# Pg07__DDR3_Memory.net
KiCad netlist of a schematic drawn in Altium Designer
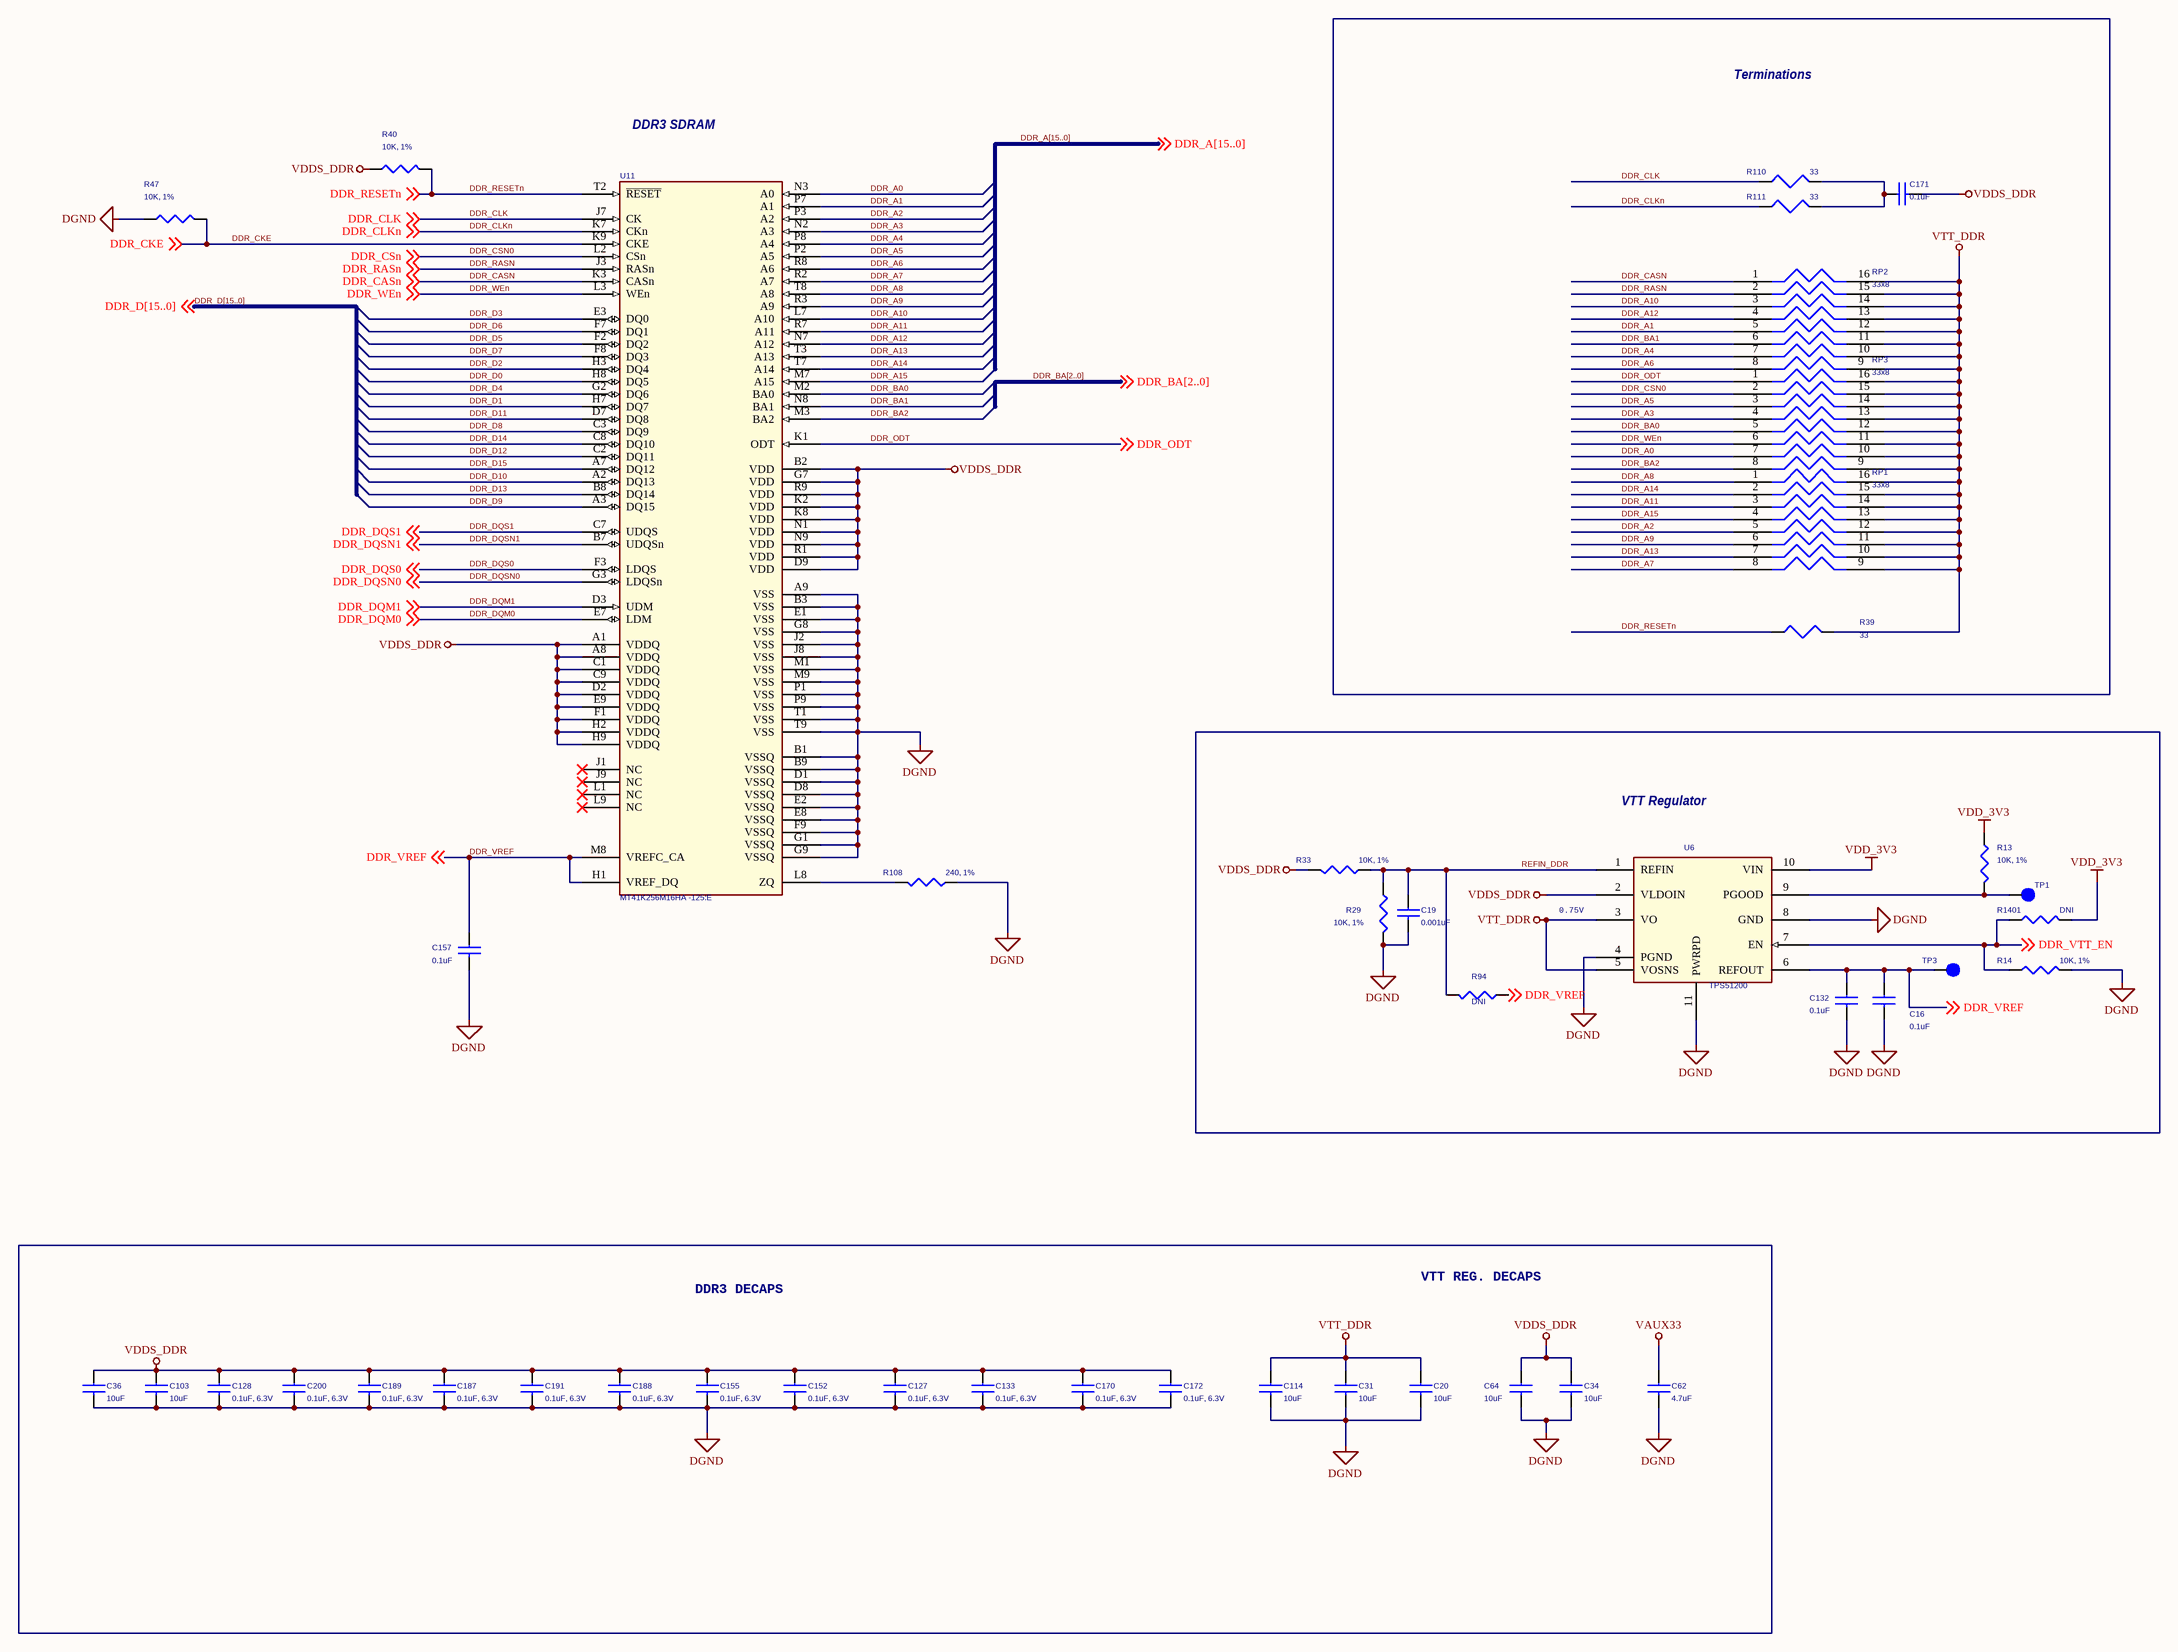
[diagram p0: Pg07_ DDR3_Memory.SchDoc]

(export (version "E")
  (design (tool "Eeschema 10.0.6"))
  (components
    (comp (ref "C16")
      (value "0.1uF")
      (footprint "SM-7351-CAP-0402")
      (fields (field (name "TIINTPARTNUMBER") "1C0089") (field (name "MFR") "Kemet"))
      (libsource (lib "*") (part "0.1uFCapacitor16V10%0402_Dup1"))
    )
    (comp (ref "C19")
      (value "0.001uF")
      (footprint "SM-7351-CAP-0402")
      (fields (field (name "MFR") "AVX") (field (name "TIINTPARTNUMBER") "1C0093"))
      (libsource (lib "*") (part "0.001uFCapacitor50V5%0402"))
    )
    (comp (ref "C20")
      (value "10uF")
      (footprint "SM-7351-CAP-0805")
      (description "Capacitor 10uF 16V 10% Ceramic 0805")
      (fields (field (name "MFR") "AVX") (field (name "TIINTPARTNUMBER") "1C0085"))
      (libsource (lib "*") (part "10uFCapacitor16V10%0805"))
    )
    (comp (ref "C31")
      (value "10uF")
      (footprint "SM-7351-CAP-0805")
      (description "Capacitor 10uF 16V 10% Ceramic 0805")
      (fields (field (name "MFR") "AVX") (field (name "TIINTPARTNUMBER") "1C0085"))
      (libsource (lib "*") (part "10uFCapacitor16V10%0805"))
    )
    (comp (ref "C34")
      (value "10uF")
      (footprint "SM-7351-CAP-0805")
      (description "Capacitor 10uF 16V 10% Ceramic 0805")
      (fields (field (name "MFR") "AVX") (field (name "TIINTPARTNUMBER") "1C0085"))
      (libsource (lib "*") (part "10uFCapacitor16V10%0805"))
    )
    (comp (ref "C36")
      (value "10uF")
      (footprint "SM-7351-CAP-0805")
      (description "Capacitor 10uF 16V 10% Ceramic 0805")
      (fields (field (name "MFR") "AVX") (field (name "TIINTPARTNUMBER") "1C0085"))
      (libsource (lib "*") (part "10uFCapacitor16V10%0805"))
    )
    (comp (ref "C62")
      (value "4.7uF")
      (footprint "SM-7351-CAP-0603")
      (fields (field (name "TIINTPARTNUMBER") "1C0103") (field (name "MFR") "Taiyo Yuden"))
      (libsource (lib "*") (part "4.7uFCapacitor16V10%0603"))
    )
    (comp (ref "C64")
      (value "10uF")
      (footprint "SM-7351-CAP-0805")
      (description "Capacitor 10uF 16V 10% Ceramic 0805")
      (fields (field (name "MFR") "AVX") (field (name "TIINTPARTNUMBER") "1C0085"))
      (libsource (lib "*") (part "10uFCapacitor16V10%0805"))
    )
    (comp (ref "C103")
      (value "10uF")
      (footprint "SM-7351-CAP-0805")
      (description "Capacitor 10uF 16V 10% Ceramic 0805")
      (fields (field (name "MFR") "AVX") (field (name "TIINTPARTNUMBER") "1C0085"))
      (libsource (lib "*") (part "10uFCapacitor16V10%0805"))
    )
    (comp (ref "C114")
      (value "10uF")
      (footprint "SM-7351-CAP-0805")
      (description "Capacitor 10uF 16V 10% Ceramic 0805")
      (fields (field (name "MFR") "AVX") (field (name "TIINTPARTNUMBER") "1C0085"))
      (libsource (lib "*") (part "10uFCapacitor16V10%0805"))
    )
    (comp (ref "C127")
      (value "0.1uF, 6.3V")
      (footprint "SM-7351-CAP-0402")
      (fields (field (name "MFR") "Murata") (field (name "TIINTPARTNUMBER") "1C0122"))
      (libsource (lib "*") (part "0.1uFCapacitor6.3V10%0201"))
    )
    (comp (ref "C128")
      (value "0.1uF, 6.3V")
      (footprint "SM-7351-CAP-0402")
      (fields (field (name "MFR") "Murata") (field (name "TIINTPARTNUMBER") "1C0122"))
      (libsource (lib "*") (part "0.1uFCapacitor6.3V10%0201"))
    )
    (comp (ref "C132")
      (value "0.1uF")
      (footprint "SM-7351-CAP-0402")
      (fields (field (name "TIINTPARTNUMBER") "1C0089") (field (name "MFR") "Kemet"))
      (libsource (lib "*") (part "0.1uFCapacitor16V10%0402_Dup1"))
    )
    (comp (ref "C133")
      (value "0.1uF, 6.3V")
      (footprint "SMD0201")
      (fields (field (name "MFR") "Murata") (field (name "TIINTPARTNUMBER") "1C0122"))
      (libsource (lib "*") (part "0.1uFCapacitor6.3V10%0201"))
    )
    (comp (ref "C152")
      (value "0.1uF, 6.3V")
      (footprint "SM-7351-CAP-0402")
      (fields (field (name "MFR") "Murata") (field (name "TIINTPARTNUMBER") "1C0122"))
      (libsource (lib "*") (part "0.1uFCapacitor6.3V10%0201"))
    )
    (comp (ref "C155")
      (value "0.1uF, 6.3V")
      (footprint "SMD0201")
      (fields (field (name "MFR") "Murata") (field (name "TIINTPARTNUMBER") "1C0122"))
      (libsource (lib "*") (part "0.1uFCapacitor6.3V10%0201"))
    )
    (comp (ref "C157")
      (value "0.1uF")
      (footprint "SM-7351-CAP-0402")
      (fields (field (name "TIINTPARTNUMBER") "1C0089") (field (name "MFR") "Kemet"))
      (libsource (lib "*") (part "0.1uFCapacitor16V10%0402_Dup1"))
    )
    (comp (ref "C170")
      (value "0.1uF, 6.3V")
      (footprint "SM-7351-CAP-0402")
      (fields (field (name "MFR") "Murata") (field (name "TIINTPARTNUMBER") "1C0122"))
      (libsource (lib "*") (part "0.1uFCapacitor6.3V10%0201"))
    )
    (comp (ref "C171")
      (value "0.1uF")
      (footprint "SM-7351-CAP-0402")
      (fields (field (name "TIINTPARTNUMBER") "1C0089") (field (name "MFR") "Kemet"))
      (libsource (lib "*") (part "0.1uFCapacitor16V10%0402_Dup1"))
    )
    (comp (ref "C172")
      (value "0.1uF, 6.3V")
      (footprint "SM-7351-CAP-0402")
      (fields (field (name "MFR") "Murata") (field (name "TIINTPARTNUMBER") "1C0122"))
      (libsource (lib "*") (part "0.1uFCapacitor6.3V10%0201"))
    )
    (comp (ref "C187")
      (value "0.1uF, 6.3V")
      (footprint "SM-7351-CAP-0402")
      (fields (field (name "MFR") "Murata") (field (name "TIINTPARTNUMBER") "1C0122"))
      (libsource (lib "*") (part "0.1uFCapacitor6.3V10%0201"))
    )
    (comp (ref "C188")
      (value "0.1uF, 6.3V")
      (footprint "SM-7351-CAP-0402")
      (fields (field (name "MFR") "Murata") (field (name "TIINTPARTNUMBER") "1C0122"))
      (libsource (lib "*") (part "0.1uFCapacitor6.3V10%0201"))
    )
    (comp (ref "C189")
      (value "0.1uF, 6.3V")
      (footprint "SM-7351-CAP-0402")
      (fields (field (name "MFR") "Murata") (field (name "TIINTPARTNUMBER") "1C0122"))
      (libsource (lib "*") (part "0.1uFCapacitor6.3V10%0201"))
    )
    (comp (ref "C191")
      (value "0.1uF, 6.3V")
      (footprint "SM-7351-CAP-0402")
      (fields (field (name "MFR") "Murata") (field (name "TIINTPARTNUMBER") "1C0122"))
      (libsource (lib "*") (part "0.1uFCapacitor6.3V10%0201"))
    )
    (comp (ref "C200")
      (value "0.1uF, 6.3V")
      (footprint "SMD0201")
      (fields (field (name "MFR") "Murata") (field (name "TIINTPARTNUMBER") "1C0122"))
      (libsource (lib "*") (part "0.1uFCapacitor6.3V10%0201"))
    )
    (comp (ref "R13")
      (value "10K, 1%")
      (footprint "SM-7351-RES-0402")
      (fields (field (name "TIINTPARTNUMBER") "1R0254") (field (name "MFR") "Panasonic-ECG"))
      (libsource (lib "*") (part "10KOhmResistor1/10W1%0402_Dup3"))
    )
    (comp (ref "R14")
      (value "10K, 1%")
      (footprint "SM-7351-RES-0402")
      (fields (field (name "TIINTPARTNUMBER") "1R0254") (field (name "MFR") "Panasonic-ECG"))
      (libsource (lib "*") (part "10KOhmResistor1/10W1%0402"))
    )
    (comp (ref "R29")
      (value "10K, 1%")
      (footprint "SM-7351-RES-0402")
      (fields (field (name "TIINTPARTNUMBER") "1R0254") (field (name "MFR") "Panasonic-ECG"))
      (libsource (lib "*") (part "10KOhmResistor1/10W1%0402_Dup3"))
    )
    (comp (ref "R33")
      (value "10K, 1%")
      (footprint "SM-7351-RES-0402")
      (fields (field (name "TIINTPARTNUMBER") "1R0254") (field (name "MFR") "Panasonic-ECG"))
      (libsource (lib "*") (part "10KOhmResistor1/10W1%0402_Dup3"))
    )
    (comp (ref "R39")
      (value "33")
      (footprint "SM-7351-RES-0402")
      (description "Resistor 33ohm 1/16W 5% 0402")
      (fields (field (name "MFR") "Panasonic") (field (name "TIINTPARTNUMBER") "1R0008"))
      (libsource (lib "*") (part "33ohmResistor1/16W5%0402"))
    )
    (comp (ref "R40")
      (value "10K, 1%")
      (footprint "SM-7351-RES-0402")
      (fields (field (name "TIINTPARTNUMBER") "1R0254") (field (name "MFR") "PANASONIC-ECG"))
      (libsource (lib "*") (part "10KOhmResistor1/10W1%0402_Dup1"))
    )
    (comp (ref "R47")
      (value "10K, 1%")
      (footprint "SM-7351-RES-0402")
      (fields (field (name "TIINTPARTNUMBER") "1R0254") (field (name "MFR") "PANASONIC-ECG"))
      (libsource (lib "*") (part "10KOhmResistor1/10W1%0402_Dup1"))
    )
    (comp (ref "R94")
      (value "DNI")
      (footprint "SM-7351-RES-0402")
      (fields (field (name "TIINTPARTNUMBER") "1R0254") (field (name "MFR") "Panasonic-ECG"))
      (libsource (lib "*") (part "10KOhmResistor1/10W1%0402_Dup3"))
    )
    (comp (ref "R108")
      (value "240, 1%")
      (footprint "SM-7351-RES-0402")
      (fields (field (name "MFR") "Panasonic-ECG") (field (name "TIINTPARTNUMBER") "1R0249"))
      (libsource (lib "*") (part "240OhmResistor1/10W1%0402"))
    )
    (comp (ref "R110")
      (value "33")
      (footprint "SM-7351-RES-0402")
      (description "Resistor 33ohm 1/16W 5% 0402")
      (fields (field (name "MFR") "Panasonic") (field (name "TIINTPARTNUMBER") "1R0008"))
      (libsource (lib "*") (part "33ohmResistor1/16W5%0402"))
    )
    (comp (ref "R111")
      (value "33")
      (footprint "SM-7351-RES-0402")
      (description "Resistor 33ohm 1/16W 5% 0402")
      (fields (field (name "MFR") "Panasonic") (field (name "TIINTPARTNUMBER") "1R0008"))
      (libsource (lib "*") (part "33ohmResistor1/16W5%0402"))
    )
    (comp (ref "R1401")
      (value "DNI")
      (footprint "SM-7351-RES-0402")
      (fields (field (name "TIINTPARTNUMBER") "1R0254") (field (name "MFR") "Panasonic-ECG"))
      (libsource (lib "*") (part "10KOhmResistor1/10W1%0402"))
    )
    (comp (ref "RP1")
      (value "33x8")
      (footprint "sm_rpak_exb-2hv")
      (description "Resistor 33ohmx8 1/16W 5% Array SMD")
      (fields (field (name "MFR") "Panasonic") (field (name "TIINTPARTNUMBER") "1R0196"))
      (libsource (lib "*") (part "33ohmx8_1/16W5%smd"))
    )
    (comp (ref "RP2")
      (value "33x8")
      (footprint "sm_rpak_exb-2hv")
      (description "Resistor 33ohmx8 1/16W 5% Array SMD")
      (fields (field (name "MFR") "Panasonic") (field (name "TIINTPARTNUMBER") "1R0196"))
      (libsource (lib "*") (part "33ohmx8_1/16W5%smd"))
    )
    (comp (ref "RP3")
      (value "33x8")
      (footprint "sm_rpak_exb-2hv")
      (description "Resistor 33ohmx8 1/16W 5% Array SMD")
      (fields (field (name "MFR") "Panasonic") (field (name "TIINTPARTNUMBER") "1R0196"))
      (libsource (lib "*") (part "33ohmx8_1/16W5%smd"))
    )
    (comp (ref "TP1")
      (value "TP1mm")
      (footprint "tp_smd1mmcircle")
      (description "Testpoint SMD 1mm circle pad")
      (fields (field (name "TIINTPARTNUMBER") "2H0046"))
      (libsource (lib "*") (part "Testpoint_SMD1mmCircle"))
    )
    (comp (ref "TP3")
      (value "TP1mm")
      (footprint "tp_smd1mmcircle")
      (description "Testpoint SMD 1mm circle pad")
      (fields (field (name "TIINTPARTNUMBER") "2H0046"))
      (libsource (lib "*") (part "Testpoint_SMD1mmCircle"))
    )
    (comp (ref "U6")
      (value "TPS51200")
      (footprint "SON10")
      (fields (field (name "TIINTPARTNUMBER") "1A0297") (field (name "MFR") "TI"))
      (libsource (lib "*") (part "TPS51200"))
    )
    (comp (ref "U11")
      (value "MT41K256M16HA -125:E")
      (footprint "BGA14X10-96")
      (description "DDR2 SDRAM 2Gb (256Mx8)")
      (fields
        (field (name "MANUFACTURER") "Micron Technology")
        (field (name "MANUFACTURER PART NUMBER") "MT41K256M16HA-125:E")
      )
      (libsource (lib "BEAGLEBONEBLACK_REV A5B") (part "MT41K256M16HA"))
    )
  )
  (nets
    (net (code "1") (name "/REFIN_DDR") (class "Default")
      (node (ref "C19") (pin "1") (pinfunction "1_1") (pintype "passive"))
      (node (ref "R29") (pin "1") (pinfunction "1_1") (pintype "passive"))
      (node (ref "R33") (pin "1") (pinfunction "1_1") (pintype "passive"))
      (node (ref "R94") (pin "2") (pinfunction "2_2") (pintype "passive"))
      (node (ref "U6") (pin "1") (pinfunction "REFIN_1") (pintype "passive"))
    )
    (net (code "2") (name "DDR_A0") (class "Default")
      (node (ref "RP3") (pin "7") (pinfunction "7_7") (pintype "passive"))
      (node (ref "U11") (pin "N3") (pinfunction "A0_N3") (pintype "input"))
    )
    (net (code "3") (name "DDR_A1") (class "Default")
      (node (ref "RP2") (pin "5") (pinfunction "5_5") (pintype "passive"))
      (node (ref "U11") (pin "P7") (pinfunction "A1_P7") (pintype "input"))
    )
    (net (code "4") (name "DDR_A2") (class "Default")
      (node (ref "RP1") (pin "5") (pinfunction "5_5") (pintype "passive"))
      (node (ref "U11") (pin "P3") (pinfunction "A2_P3") (pintype "input"))
    )
    (net (code "5") (name "DDR_A3") (class "Default")
      (node (ref "RP3") (pin "4") (pinfunction "4_4") (pintype "passive"))
      (node (ref "U11") (pin "N2") (pinfunction "A3_N2") (pintype "input"))
    )
    (net (code "6") (name "DDR_A4") (class "Default")
      (node (ref "RP2") (pin "7") (pinfunction "7_7") (pintype "passive"))
      (node (ref "U11") (pin "P8") (pinfunction "A4_P8") (pintype "input"))
    )
    (net (code "7") (name "DDR_A5") (class "Default")
      (node (ref "RP3") (pin "3") (pinfunction "3_3") (pintype "passive"))
      (node (ref "U11") (pin "P2") (pinfunction "A5_P2") (pintype "input"))
    )
    (net (code "8") (name "DDR_A6") (class "Default")
      (node (ref "RP2") (pin "8") (pinfunction "8_8") (pintype "passive"))
      (node (ref "U11") (pin "R8") (pinfunction "A6_R8") (pintype "input"))
    )
    (net (code "9") (name "DDR_A7") (class "Default")
      (node (ref "RP1") (pin "8") (pinfunction "8_8") (pintype "passive"))
      (node (ref "U11") (pin "R2") (pinfunction "A7_R2") (pintype "input"))
    )
    (net (code "10") (name "DDR_A8") (class "Default")
      (node (ref "RP1") (pin "1") (pinfunction "1_1") (pintype "passive"))
      (node (ref "U11") (pin "T8") (pinfunction "A8_T8") (pintype "input"))
    )
    (net (code "11") (name "DDR_A9") (class "Default")
      (node (ref "RP1") (pin "6") (pinfunction "6_6") (pintype "passive"))
      (node (ref "U11") (pin "R3") (pinfunction "A9_R3") (pintype "input"))
    )
    (net (code "12") (name "DDR_A10") (class "Default")
      (node (ref "RP2") (pin "3") (pinfunction "3_3") (pintype "passive"))
      (node (ref "U11") (pin "L7") (pinfunction "A10_L7") (pintype "input"))
    )
    (net (code "13") (name "DDR_A11") (class "Default")
      (node (ref "RP1") (pin "3") (pinfunction "3_3") (pintype "passive"))
      (node (ref "U11") (pin "R7") (pinfunction "A11_R7") (pintype "input"))
    )
    (net (code "14") (name "DDR_A12") (class "Default")
      (node (ref "RP2") (pin "4") (pinfunction "4_4") (pintype "passive"))
      (node (ref "U11") (pin "N7") (pinfunction "A12_N7") (pintype "input"))
    )
    (net (code "15") (name "DDR_A13") (class "Default")
      (node (ref "RP1") (pin "7") (pinfunction "7_7") (pintype "passive"))
      (node (ref "U11") (pin "T3") (pinfunction "A13_T3") (pintype "input"))
    )
    (net (code "16") (name "DDR_A14") (class "Default")
      (node (ref "RP1") (pin "2") (pinfunction "2_2") (pintype "passive"))
      (node (ref "U11") (pin "T7") (pinfunction "A14_T7") (pintype "input"))
    )
    (net (code "17") (name "DDR_A15") (class "Default")
      (node (ref "RP1") (pin "4") (pinfunction "4_4") (pintype "passive"))
      (node (ref "U11") (pin "M7") (pinfunction "A15_M7") (pintype "input"))
    )
    (net (code "19") (name "DDR_BA0") (class "Default")
      (node (ref "RP3") (pin "5") (pinfunction "5_5") (pintype "passive"))
      (node (ref "U11") (pin "M2") (pinfunction "BA0_M2") (pintype "input"))
    )
    (net (code "20") (name "DDR_BA1") (class "Default")
      (node (ref "RP2") (pin "6") (pinfunction "6_6") (pintype "passive"))
      (node (ref "U11") (pin "N8") (pinfunction "BA1_N8") (pintype "input"))
    )
    (net (code "21") (name "DDR_BA2") (class "Default")
      (node (ref "RP3") (pin "8") (pinfunction "8_8") (pintype "passive"))
      (node (ref "U11") (pin "M3") (pinfunction "BA2_M3") (pintype "input"))
    )
    (net (code "23") (name "DDR_CASn") (class "Default")
      (node (ref "RP2") (pin "1") (pinfunction "1_1") (pintype "passive"))
      (node (ref "U11") (pin "K3") (pinfunction "CASn_K3") (pintype "input"))
    )
    (net (code "24") (name "DDR_CKE") (class "Default")
      (node (ref "R47") (pin "2") (pinfunction "2_2") (pintype "passive"))
      (node (ref "U11") (pin "K9") (pinfunction "CKE_K9") (pintype "input"))
    )
    (net (code "25") (name "DDR_CLK") (class "Default")
      (node (ref "R110") (pin "1") (pinfunction "1_1") (pintype "passive"))
      (node (ref "U11") (pin "J7") (pinfunction "CK_J7") (pintype "input"))
    )
    (net (code "26") (name "DDR_CLKn") (class "Default")
      (node (ref "R111") (pin "1") (pinfunction "1_1") (pintype "passive"))
      (node (ref "U11") (pin "K7") (pinfunction "CKn_K7") (pintype "input"))
    )
    (net (code "27") (name "DDR_CSn") (class "Default")
      (node (ref "RP3") (pin "2") (pinfunction "2_2") (pintype "passive"))
      (node (ref "U11") (pin "L2") (pinfunction "CSn_L2") (pintype "input"))
    )
    (net (code "28") (name "DDR_D0") (class "Default")
      (node (ref "U11") (pin "H8") (pinfunction "DQ5_H8") (pintype "bidirectional"))
    )
    (net (code "29") (name "DDR_D1") (class "Default")
      (node (ref "U11") (pin "H7") (pinfunction "DQ7_H7") (pintype "bidirectional"))
    )
    (net (code "30") (name "DDR_D2") (class "Default")
      (node (ref "U11") (pin "H3") (pinfunction "DQ4_H3") (pintype "bidirectional"))
    )
    (net (code "31") (name "DDR_D3") (class "Default")
      (node (ref "U11") (pin "E3") (pinfunction "DQ0_E3") (pintype "bidirectional"))
    )
    (net (code "32") (name "DDR_D4") (class "Default")
      (node (ref "U11") (pin "G2") (pinfunction "DQ6_G2") (pintype "bidirectional"))
    )
    (net (code "33") (name "DDR_D5") (class "Default")
      (node (ref "U11") (pin "F2") (pinfunction "DQ2_F2") (pintype "bidirectional"))
    )
    (net (code "34") (name "DDR_D6") (class "Default")
      (node (ref "U11") (pin "F7") (pinfunction "DQ1_F7") (pintype "bidirectional"))
    )
    (net (code "35") (name "DDR_D7") (class "Default")
      (node (ref "U11") (pin "F8") (pinfunction "DQ3_F8") (pintype "bidirectional"))
    )
    (net (code "36") (name "DDR_D8") (class "Default")
      (node (ref "U11") (pin "C3") (pinfunction "DQ9_C3") (pintype "bidirectional"))
    )
    (net (code "37") (name "DDR_D9") (class "Default")
      (node (ref "U11") (pin "A3") (pinfunction "DQ15_A3") (pintype "bidirectional"))
    )
    (net (code "38") (name "DDR_D10") (class "Default")
      (node (ref "U11") (pin "A2") (pinfunction "DQ13_A2") (pintype "bidirectional"))
    )
    (net (code "39") (name "DDR_D11") (class "Default")
      (node (ref "U11") (pin "D7") (pinfunction "DQ8_D7") (pintype "bidirectional"))
    )
    (net (code "40") (name "DDR_D12") (class "Default")
      (node (ref "U11") (pin "C2") (pinfunction "DQ11_C2") (pintype "bidirectional"))
    )
    (net (code "41") (name "DDR_D13") (class "Default")
      (node (ref "U11") (pin "B8") (pinfunction "DQ14_B8") (pintype "bidirectional"))
    )
    (net (code "42") (name "DDR_D14") (class "Default")
      (node (ref "U11") (pin "C8") (pinfunction "DQ10_C8") (pintype "bidirectional"))
    )
    (net (code "43") (name "DDR_D15") (class "Default")
      (node (ref "U11") (pin "A7") (pinfunction "DQ12_A7") (pintype "bidirectional"))
    )
    (net (code "44") (name "DDR_DQM0") (class "Default")
      (node (ref "U11") (pin "E7") (pinfunction "LDM_E7") (pintype "bidirectional"))
    )
    (net (code "45") (name "DDR_DQM1") (class "Default")
      (node (ref "U11") (pin "D3") (pinfunction "UDM_D3") (pintype "input"))
    )
    (net (code "46") (name "DDR_DQS0") (class "Default")
      (node (ref "U11") (pin "F3") (pinfunction "LDQS_F3") (pintype "bidirectional"))
    )
    (net (code "47") (name "DDR_DQS1") (class "Default")
      (node (ref "U11") (pin "C7") (pinfunction "UDQS_C7") (pintype "bidirectional"))
    )
    (net (code "48") (name "DDR_DQSN0") (class "Default")
      (node (ref "U11") (pin "G3") (pinfunction "LDQSn_G3") (pintype "bidirectional"))
    )
    (net (code "49") (name "DDR_DQSN1") (class "Default")
      (node (ref "U11") (pin "B7") (pinfunction "UDQSn_B7") (pintype "bidirectional"))
    )
    (net (code "51") (name "DDR_ODT") (class "Default")
      (node (ref "RP3") (pin "1") (pinfunction "1_1") (pintype "passive"))
      (node (ref "U11") (pin "K1") (pinfunction "ODT_K1") (pintype "input"))
    )
    (net (code "52") (name "DDR_RASn") (class "Default")
      (node (ref "RP2") (pin "2") (pinfunction "2_2") (pintype "passive"))
      (node (ref "U11") (pin "J3") (pinfunction "RASn_J3") (pintype "input"))
    )
    (net (code "53") (name "DDR_RESETn") (class "Default")
      (node (ref "R39") (pin "1") (pinfunction "1_1") (pintype "passive"))
      (node (ref "R40") (pin "2") (pinfunction "2_2") (pintype "passive"))
      (node (ref "U11") (pin "T2") (pinfunction "~{RESET}_T2") (pintype "input"))
    )
    (net (code "54") (name "DDR_VREF") (class "Default")
      (node (ref "C132") (pin "1") (pinfunction "1_1") (pintype "passive"))
      (node (ref "C157") (pin "1") (pinfunction "1_1") (pintype "passive"))
      (node (ref "C16") (pin "1") (pinfunction "1_1") (pintype "passive"))
      (node (ref "R94") (pin "1") (pinfunction "1_1") (pintype "passive"))
      (node (ref "TP3") (pin "1") (pinfunction "1_1") (pintype "passive"))
      (node (ref "U11") (pin "H1") (pinfunction "VREF_DQ_H1") (pintype "passive"))
      (node (ref "U11") (pin "M8") (pinfunction "VREFC_CA_M8") (pintype "power_in"))
      (node (ref "U6") (pin "6") (pinfunction "REFOUT_6") (pintype "passive"))
    )
    (net (code "55") (name "DDR_VTT_EN") (class "Default")
      (node (ref "R14") (pin "1") (pinfunction "1_1") (pintype "passive"))
      (node (ref "R1401") (pin "1") (pinfunction "1_1") (pintype "passive"))
      (node (ref "U6") (pin "7") (pinfunction "EN_7") (pintype "input"))
    )
    (net (code "56") (name "DDR_WEn") (class "Default")
      (node (ref "RP3") (pin "6") (pinfunction "6_6") (pintype "passive"))
      (node (ref "U11") (pin "L3") (pinfunction "WEn_L3") (pintype "input"))
    )
    (net (code "57") (name "DGND") (class "Default")
      (node (ref "C103") (pin "2") (pinfunction "2_2") (pintype "passive"))
      (node (ref "C114") (pin "2") (pinfunction "2_2") (pintype "passive"))
      (node (ref "C127") (pin "2") (pinfunction "2_2") (pintype "passive"))
      (node (ref "C128") (pin "2") (pinfunction "2_2") (pintype "passive"))
      (node (ref "C132") (pin "2") (pinfunction "2_2") (pintype "passive"))
      (node (ref "C133") (pin "2") (pinfunction "2_2") (pintype "passive"))
      (node (ref "C152") (pin "2") (pinfunction "2_2") (pintype "passive"))
      (node (ref "C155") (pin "2") (pinfunction "2_2") (pintype "passive"))
      (node (ref "C157") (pin "2") (pinfunction "2_2") (pintype "passive"))
      (node (ref "C16") (pin "2") (pinfunction "2_2") (pintype "passive"))
      (node (ref "C170") (pin "2") (pinfunction "2_2") (pintype "passive"))
      (node (ref "C172") (pin "2") (pinfunction "2_2") (pintype "passive"))
      (node (ref "C187") (pin "2") (pinfunction "2_2") (pintype "passive"))
      (node (ref "C188") (pin "2") (pinfunction "2_2") (pintype "passive"))
      (node (ref "C189") (pin "2") (pinfunction "2_2") (pintype "passive"))
      (node (ref "C19") (pin "2") (pinfunction "2_2") (pintype "passive"))
      (node (ref "C191") (pin "2") (pinfunction "2_2") (pintype "passive"))
      (node (ref "C20") (pin "2") (pinfunction "2_2") (pintype "passive"))
      (node (ref "C200") (pin "2") (pinfunction "2_2") (pintype "passive"))
      (node (ref "C31") (pin "2") (pinfunction "2_2") (pintype "passive"))
      (node (ref "C34") (pin "2") (pinfunction "2_2") (pintype "passive"))
      (node (ref "C36") (pin "2") (pinfunction "2_2") (pintype "passive"))
      (node (ref "C62") (pin "2") (pinfunction "2_2") (pintype "passive"))
      (node (ref "C64") (pin "2") (pinfunction "2_2") (pintype "passive"))
      (node (ref "R108") (pin "1") (pinfunction "1_1") (pintype "passive"))
      (node (ref "R14") (pin "2") (pinfunction "2_2") (pintype "passive"))
      (node (ref "R29") (pin "2") (pinfunction "2_2") (pintype "passive"))
      (node (ref "R47") (pin "1") (pinfunction "1_1") (pintype "passive"))
      (node (ref "U11") (pin "A9") (pinfunction "VSS_A9") (pintype "power_in"))
      (node (ref "U11") (pin "B1") (pinfunction "VSSQ_B1") (pintype "power_in"))
      (node (ref "U11") (pin "B3") (pinfunction "VSS_B3") (pintype "power_in"))
      (node (ref "U11") (pin "B9") (pinfunction "VSSQ_B9") (pintype "power_in"))
      (node (ref "U11") (pin "D1") (pinfunction "VSSQ_D1") (pintype "power_in"))
      (node (ref "U11") (pin "D8") (pinfunction "VSSQ_D8") (pintype "power_in"))
      (node (ref "U11") (pin "E1") (pinfunction "VSS_E1") (pintype "power_in"))
      (node (ref "U11") (pin "E2") (pinfunction "VSSQ_E2") (pintype "power_in"))
      (node (ref "U11") (pin "E8") (pinfunction "VSSQ_E8") (pintype "power_in"))
      (node (ref "U11") (pin "F9") (pinfunction "VSSQ_F9") (pintype "power_in"))
      (node (ref "U11") (pin "G1") (pinfunction "VSSQ_G1") (pintype "power_in"))
      (node (ref "U11") (pin "G8") (pinfunction "VSS_G8") (pintype "power_in"))
      (node (ref "U11") (pin "G9") (pinfunction "VSSQ_G9") (pintype "power_in"))
      (node (ref "U11") (pin "J2") (pinfunction "VSS_J2") (pintype "power_in"))
      (node (ref "U11") (pin "J8") (pinfunction "VSS_J8") (pintype "power_in"))
      (node (ref "U11") (pin "M1") (pinfunction "VSS_M1") (pintype "power_in"))
      (node (ref "U11") (pin "M9") (pinfunction "VSS_M9") (pintype "power_in"))
      (node (ref "U11") (pin "P1") (pinfunction "VSS_P1") (pintype "power_in"))
      (node (ref "U11") (pin "P9") (pinfunction "VSS_P9") (pintype "power_in"))
      (node (ref "U11") (pin "T1") (pinfunction "VSS_T1") (pintype "power_in"))
      (node (ref "U11") (pin "T9") (pinfunction "VSS_T9") (pintype "power_in"))
      (node (ref "U6") (pin "11") (pinfunction "PWRPD_11") (pintype "power_in"))
      (node (ref "U6") (pin "4") (pinfunction "PGND_4") (pintype "power_in"))
      (node (ref "U6") (pin "8") (pinfunction "GND_8") (pintype "power_in"))
    )
    (net (code "58") (name "Net-(C171-Pad1)") (class "Default")
      (node (ref "C171") (pin "1") (pinfunction "1_1") (pintype "passive"))
      (node (ref "R110") (pin "2") (pinfunction "2_2") (pintype "passive"))
      (node (ref "R111") (pin "2") (pinfunction "2_2") (pintype "passive"))
    )
    (net (code "59") (name "Net-(U6-PGOOD)") (class "Default")
      (node (ref "R13") (pin "2") (pinfunction "2_2") (pintype "passive"))
      (node (ref "TP1") (pin "1") (pinfunction "1_1") (pintype "passive"))
      (node (ref "U6") (pin "9") (pinfunction "PGOOD_9") (pintype "passive"))
    )
    (net (code "60") (name "Net-(U11-ZQ)") (class "Default")
      (node (ref "R108") (pin "2") (pinfunction "2_2") (pintype "passive"))
      (node (ref "U11") (pin "L8") (pinfunction "ZQ_L8") (pintype "passive"))
    )
    (net (code "61") (name "VAUX33") (class "Default")
      (node (ref "C62") (pin "1") (pinfunction "1_1") (pintype "passive"))
    )
    (net (code "62") (name "VDDS_DDR") (class "Default")
      (node (ref "C103") (pin "1") (pinfunction "1_1") (pintype "passive"))
      (node (ref "C127") (pin "1") (pinfunction "1_1") (pintype "passive"))
      (node (ref "C128") (pin "1") (pinfunction "1_1") (pintype "passive"))
      (node (ref "C133") (pin "1") (pinfunction "1_1") (pintype "passive"))
      (node (ref "C152") (pin "1") (pinfunction "1_1") (pintype "passive"))
      (node (ref "C155") (pin "1") (pinfunction "1_1") (pintype "passive"))
      (node (ref "C170") (pin "1") (pinfunction "1_1") (pintype "passive"))
      (node (ref "C171") (pin "2") (pinfunction "2_2") (pintype "passive"))
      (node (ref "C172") (pin "1") (pinfunction "1_1") (pintype "passive"))
      (node (ref "C187") (pin "1") (pinfunction "1_1") (pintype "passive"))
      (node (ref "C188") (pin "1") (pinfunction "1_1") (pintype "passive"))
      (node (ref "C189") (pin "1") (pinfunction "1_1") (pintype "passive"))
      (node (ref "C191") (pin "1") (pinfunction "1_1") (pintype "passive"))
      (node (ref "C200") (pin "1") (pinfunction "1_1") (pintype "passive"))
      (node (ref "C34") (pin "1") (pinfunction "1_1") (pintype "passive"))
      (node (ref "C36") (pin "1") (pinfunction "1_1") (pintype "passive"))
      (node (ref "C64") (pin "1") (pinfunction "1_1") (pintype "passive"))
      (node (ref "R33") (pin "2") (pinfunction "2_2") (pintype "passive"))
      (node (ref "R40") (pin "1") (pinfunction "1_1") (pintype "passive"))
      (node (ref "U11") (pin "A1") (pinfunction "VDDQ_A1") (pintype "power_in"))
      (node (ref "U11") (pin "A8") (pinfunction "VDDQ_A8") (pintype "power_in"))
      (node (ref "U11") (pin "B2") (pinfunction "VDD_B2") (pintype "power_in"))
      (node (ref "U11") (pin "C1") (pinfunction "VDDQ_C1") (pintype "power_in"))
      (node (ref "U11") (pin "C9") (pinfunction "VDDQ_C9") (pintype "power_in"))
      (node (ref "U11") (pin "D2") (pinfunction "VDDQ_D2") (pintype "power_in"))
      (node (ref "U11") (pin "D9") (pinfunction "VDD_D9") (pintype "power_in"))
      (node (ref "U11") (pin "E9") (pinfunction "VDDQ_E9") (pintype "power_in"))
      (node (ref "U11") (pin "F1") (pinfunction "VDDQ_F1") (pintype "power_in"))
      (node (ref "U11") (pin "G7") (pinfunction "VDD_G7") (pintype "power_in"))
      (node (ref "U11") (pin "H2") (pinfunction "VDDQ_H2") (pintype "power_in"))
      (node (ref "U11") (pin "H9") (pinfunction "VDDQ_H9") (pintype "power_in"))
      (node (ref "U11") (pin "K2") (pinfunction "VDD_K2") (pintype "power_in"))
      (node (ref "U11") (pin "K8") (pinfunction "VDD_K8") (pintype "power_in"))
      (node (ref "U11") (pin "N1") (pinfunction "VDD_N1") (pintype "power_in"))
      (node (ref "U11") (pin "N9") (pinfunction "VDD_N9") (pintype "power_in"))
      (node (ref "U11") (pin "R1") (pinfunction "VDD_R1") (pintype "power_in"))
      (node (ref "U11") (pin "R9") (pinfunction "VDD_R9") (pintype "power_in"))
      (node (ref "U6") (pin "2") (pinfunction "VLDOIN_2") (pintype "passive"))
    )
    (net (code "63") (name "VDD_3V3") (class "Default")
      (node (ref "R13") (pin "1") (pinfunction "1_1") (pintype "passive"))
      (node (ref "R1401") (pin "2") (pinfunction "2_2") (pintype "passive"))
      (node (ref "U6") (pin "10") (pinfunction "VIN_10") (pintype "passive"))
    )
    (net (code "64") (name "VTT_DDR") (class "Default")
      (node (ref "C114") (pin "1") (pinfunction "1_1") (pintype "passive"))
      (node (ref "C20") (pin "1") (pinfunction "1_1") (pintype "passive"))
      (node (ref "C31") (pin "1") (pinfunction "1_1") (pintype "passive"))
      (node (ref "R39") (pin "2") (pinfunction "2_2") (pintype "passive"))
      (node (ref "RP1") (pin "10") (pinfunction "10_10") (pintype "passive"))
      (node (ref "RP1") (pin "11") (pinfunction "11_11") (pintype "passive"))
      (node (ref "RP1") (pin "12") (pinfunction "12_12") (pintype "passive"))
      (node (ref "RP1") (pin "13") (pinfunction "13_13") (pintype "passive"))
      (node (ref "RP1") (pin "14") (pinfunction "14_14") (pintype "passive"))
      (node (ref "RP1") (pin "15") (pinfunction "15_15") (pintype "passive"))
      (node (ref "RP1") (pin "16") (pinfunction "16_16") (pintype "passive"))
      (node (ref "RP1") (pin "9") (pinfunction "9_9") (pintype "passive"))
      (node (ref "RP2") (pin "10") (pinfunction "10_10") (pintype "passive"))
      (node (ref "RP2") (pin "11") (pinfunction "11_11") (pintype "passive"))
      (node (ref "RP2") (pin "12") (pinfunction "12_12") (pintype "passive"))
      (node (ref "RP2") (pin "13") (pinfunction "13_13") (pintype "passive"))
      (node (ref "RP2") (pin "14") (pinfunction "14_14") (pintype "passive"))
      (node (ref "RP2") (pin "15") (pinfunction "15_15") (pintype "passive"))
      (node (ref "RP2") (pin "16") (pinfunction "16_16") (pintype "passive"))
      (node (ref "RP2") (pin "9") (pinfunction "9_9") (pintype "passive"))
      (node (ref "RP3") (pin "10") (pinfunction "10_10") (pintype "passive"))
      (node (ref "RP3") (pin "11") (pinfunction "11_11") (pintype "passive"))
      (node (ref "RP3") (pin "12") (pinfunction "12_12") (pintype "passive"))
      (node (ref "RP3") (pin "13") (pinfunction "13_13") (pintype "passive"))
      (node (ref "RP3") (pin "14") (pinfunction "14_14") (pintype "passive"))
      (node (ref "RP3") (pin "15") (pinfunction "15_15") (pintype "passive"))
      (node (ref "RP3") (pin "16") (pinfunction "16_16") (pintype "passive"))
      (node (ref "RP3") (pin "9") (pinfunction "9_9") (pintype "passive"))
      (node (ref "U6") (pin "3") (pinfunction "VO_3") (pintype "passive"))
      (node (ref "U6") (pin "5") (pinfunction "VOSNS_5") (pintype "passive"))
    )
    (net (code "65") (name "unconnected-(U11-NC-PadJ1)") (class "Default")
      (node (ref "U11") (pin "J1") (pinfunction "NC_J1") (pintype "passive+no_connect"))
    )
    (net (code "66") (name "unconnected-(U11-NC-PadJ9)") (class "Default")
      (node (ref "U11") (pin "J9") (pinfunction "NC_J9") (pintype "passive+no_connect"))
    )
    (net (code "67") (name "unconnected-(U11-NC-PadL1)") (class "Default")
      (node (ref "U11") (pin "L1") (pinfunction "NC_L1") (pintype "power_in+no_connect"))
    )
    (net (code "68") (name "unconnected-(U11-NC-PadL9)") (class "Default")
      (node (ref "U11") (pin "L9") (pinfunction "NC_L9") (pintype "power_in+no_connect"))
    )
  )
)
